# 1-Schematic_electronic_khipu_2.net
KiCad netlist of a schematic drawn in EasyEDA
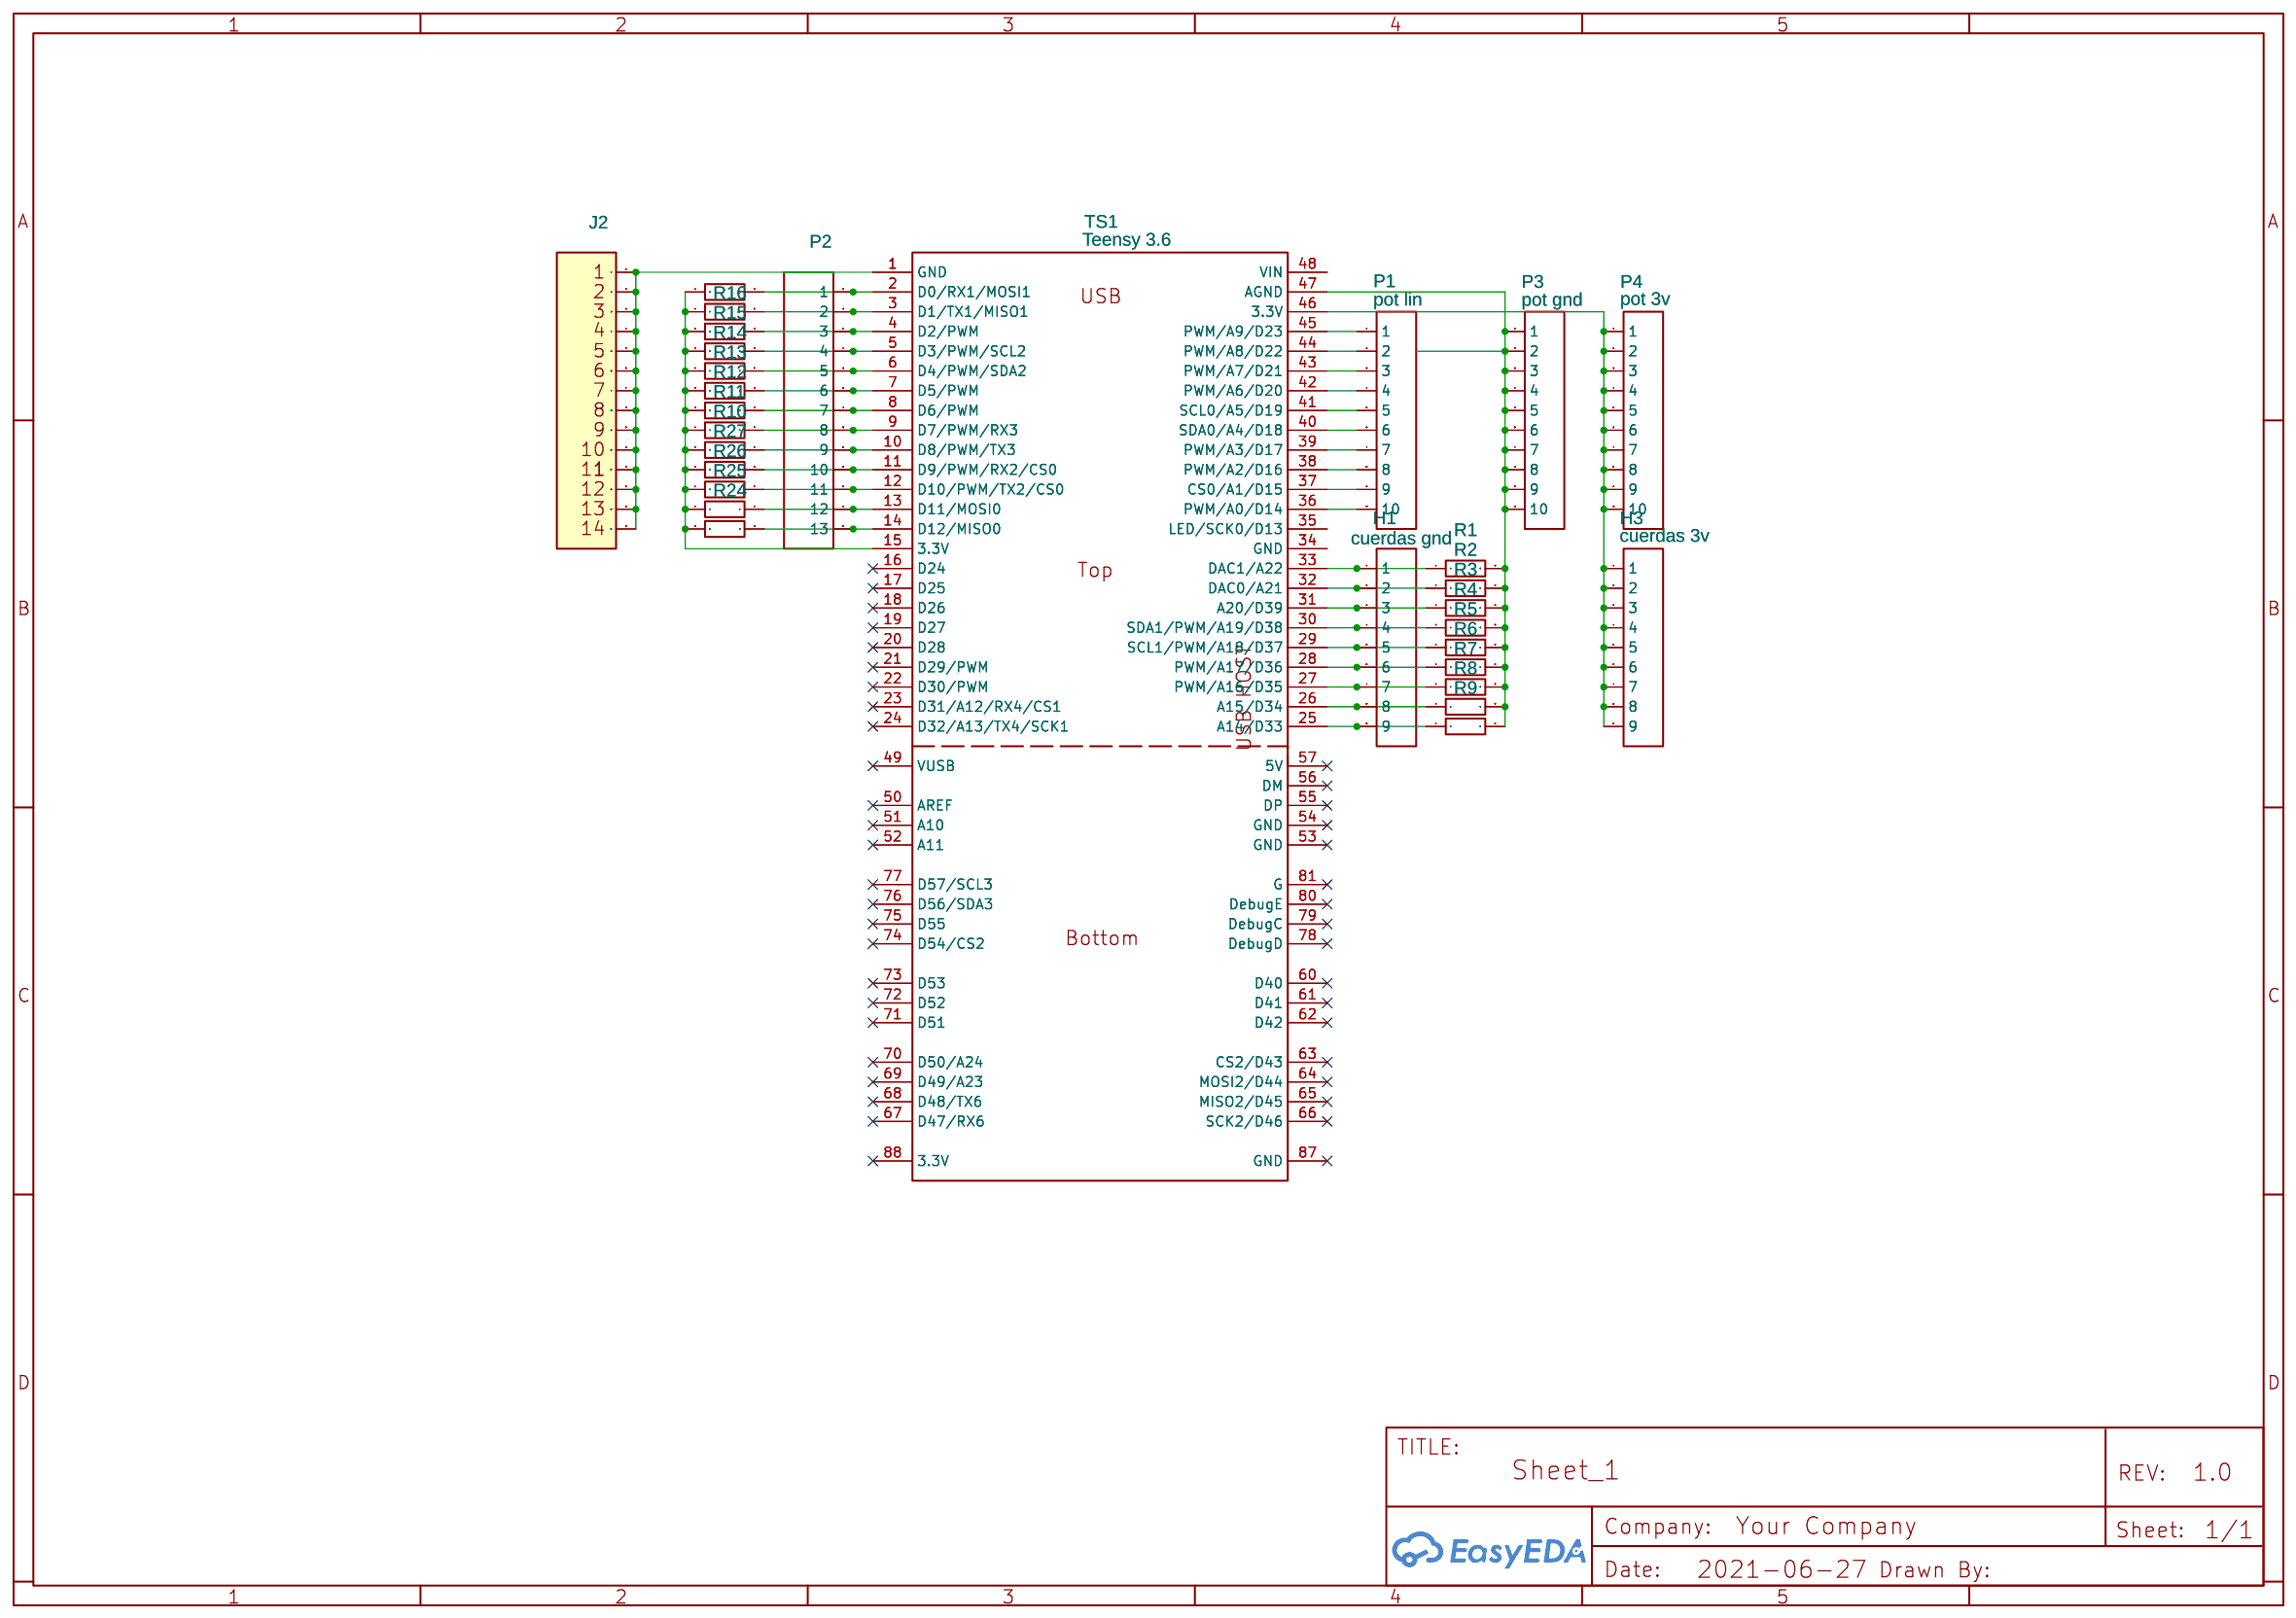
[diagram p0: schematic sheet]

(export (version "E")
  (design (tool "Eeschema 10.0.6"))
  (components
    (comp (ref "H1")
      (value "cuerdas gnd")
      (fields
        (field (name "BOM_Manufacturer Part") "2.54mm 1*9 Straight Female header")
        (field (name "BOM_Supplier Part") "C39576")
      )
      (libsource (lib "") (part "Header-Female-2.54_1x9"))
    )
    (comp (ref "H3")
      (value "cuerdas 3v")
      (fields
        (field (name "BOM_Manufacturer Part") "2.54mm 1*9 Straight Female header")
        (field (name "BOM_Supplier Part") "C39576")
      )
      (libsource (lib "") (part "Header-Female-2.54_1x9"))
    )
    (comp (ref "J2") (value "Header_Female_1x14") (libsource (lib "") (part "Header_Female_1x14")))
    (comp (ref "P1")
      (value "pot lin")
      (fields
        (field (name "BOM_Manufacturer Part") "2.54mm 1*10P Straight Female header Gold-plated")
        (field (name "BOM_Supplier Part") "C35445")
      )
      (libsource (lib "") (part "Header-Female-2.54_1x10-TEST"))
    )
    (comp (ref "P2")
      (value "Header-Female-2.54_1x13")
      (fields
        (field (name "BOM_Manufacturer Part") "Female header 2.54-1*13P")
        (field (name "BOM_Supplier Part") "C52709")
      )
      (libsource (lib "") (part "Header-Female-2.54_1x13"))
    )
    (comp (ref "P3")
      (value "pot gnd")
      (fields
        (field (name "BOM_Manufacturer Part") "2.54mm 1*10P Straight Female header Gold-plated")
        (field (name "BOM_Supplier Part") "C35445")
      )
      (libsource (lib "") (part "Header-Female-2.54_1x10-TEST"))
    )
    (comp (ref "P4")
      (value "pot 3v")
      (fields
        (field (name "BOM_Manufacturer Part") "2.54mm 1*10P Straight Female header Gold-plated")
        (field (name "BOM_Supplier Part") "C35445")
      )
      (libsource (lib "") (part "Header-Female-2.54_1x10-TEST"))
    )
    (comp (ref "R1")
      (value "10K")
      (fields
        (field (name "BOM_Manufacturer Part") "PTFR0603B10K0P9")
        (field (name "BOM_Supplier Part") "C328421")
      )
      (libsource (lib "") (part "PTFR0603B10K0P9"))
    )
    (comp (ref "R2")
      (value "10K")
      (fields
        (field (name "BOM_Manufacturer Part") "PTFR0603B10K0P9")
        (field (name "BOM_Supplier Part") "C328421")
      )
      (libsource (lib "") (part "PTFR0603B10K0P9"))
    )
    (comp (ref "R3")
      (value "10K")
      (fields
        (field (name "BOM_Manufacturer Part") "PTFR0603B10K0P9")
        (field (name "BOM_Supplier Part") "C328421")
      )
      (libsource (lib "") (part "PTFR0603B10K0P9"))
    )
    (comp (ref "R4")
      (value "10K")
      (fields
        (field (name "BOM_Manufacturer Part") "PTFR0603B10K0P9")
        (field (name "BOM_Supplier Part") "C328421")
      )
      (libsource (lib "") (part "PTFR0603B10K0P9"))
    )
    (comp (ref "R5")
      (value "10K")
      (fields
        (field (name "BOM_Manufacturer Part") "PTFR0603B10K0P9")
        (field (name "BOM_Supplier Part") "C328421")
      )
      (libsource (lib "") (part "PTFR0603B10K0P9"))
    )
    (comp (ref "R6")
      (value "10K")
      (fields
        (field (name "BOM_Manufacturer Part") "PTFR0603B10K0P9")
        (field (name "BOM_Supplier Part") "C328421")
      )
      (libsource (lib "") (part "PTFR0603B10K0P9"))
    )
    (comp (ref "R7")
      (value "10K")
      (fields
        (field (name "BOM_Manufacturer Part") "PTFR0603B10K0P9")
        (field (name "BOM_Supplier Part") "C328421")
      )
      (libsource (lib "") (part "PTFR0603B10K0P9"))
    )
    (comp (ref "R8")
      (value "10K")
      (fields
        (field (name "BOM_Manufacturer Part") "PTFR0603B10K0P9")
        (field (name "BOM_Supplier Part") "C328421")
      )
      (libsource (lib "") (part "PTFR0603B10K0P9"))
    )
    (comp (ref "R9")
      (value "10K")
      (fields
        (field (name "BOM_Manufacturer Part") "PTFR0603B10K0P9")
        (field (name "BOM_Supplier Part") "C328421")
      )
      (libsource (lib "") (part "PTFR0603B10K0P9"))
    )
    (comp (ref "R10")
      (value "10K")
      (fields
        (field (name "BOM_Manufacturer Part") "PTFR0603B10K0P9")
        (field (name "BOM_Supplier Part") "C328421")
      )
      (libsource (lib "") (part "PTFR0603B10K0P9"))
    )
    (comp (ref "R11")
      (value "10K")
      (fields
        (field (name "BOM_Manufacturer Part") "PTFR0603B10K0P9")
        (field (name "BOM_Supplier Part") "C328421")
      )
      (libsource (lib "") (part "PTFR0603B10K0P9"))
    )
    (comp (ref "R12")
      (value "10K")
      (fields
        (field (name "BOM_Manufacturer Part") "PTFR0603B10K0P9")
        (field (name "BOM_Supplier Part") "C328421")
      )
      (libsource (lib "") (part "PTFR0603B10K0P9"))
    )
    (comp (ref "R13")
      (value "10K")
      (fields
        (field (name "BOM_Manufacturer Part") "PTFR0603B10K0P9")
        (field (name "BOM_Supplier Part") "C328421")
      )
      (libsource (lib "") (part "PTFR0603B10K0P9"))
    )
    (comp (ref "R14")
      (value "10K")
      (fields
        (field (name "BOM_Manufacturer Part") "PTFR0603B10K0P9")
        (field (name "BOM_Supplier Part") "C328421")
      )
      (libsource (lib "") (part "PTFR0603B10K0P9"))
    )
    (comp (ref "R15")
      (value "10K")
      (fields
        (field (name "BOM_Manufacturer Part") "PTFR0603B10K0P9")
        (field (name "BOM_Supplier Part") "C328421")
      )
      (libsource (lib "") (part "PTFR0603B10K0P9"))
    )
    (comp (ref "R16")
      (value "10K")
      (fields
        (field (name "BOM_Manufacturer Part") "PTFR0603B10K0P9")
        (field (name "BOM_Supplier Part") "C328421")
      )
      (libsource (lib "") (part "PTFR0603B10K0P9"))
    )
    (comp (ref "R17")
      (value "10K")
      (fields
        (field (name "BOM_Manufacturer Part") "PTFR0603B10K0P9")
        (field (name "BOM_Supplier Part") "C328421")
      )
      (libsource (lib "") (part "PTFR0603B10K0P9"))
    )
    (comp (ref "R18")
      (value "10K")
      (fields
        (field (name "BOM_Manufacturer Part") "PTFR0603B10K0P9")
        (field (name "BOM_Supplier Part") "C328421")
      )
      (libsource (lib "") (part "PTFR0603B10K0P9"))
    )
    (comp (ref "R24")
      (value "10K")
      (fields
        (field (name "BOM_Manufacturer Part") "PTFR0603B10K0P9")
        (field (name "BOM_Supplier Part") "C328421")
      )
      (libsource (lib "") (part "PTFR0603B10K0P9"))
    )
    (comp (ref "R25")
      (value "10K")
      (fields
        (field (name "BOM_Manufacturer Part") "PTFR0603B10K0P9")
        (field (name "BOM_Supplier Part") "C328421")
      )
      (libsource (lib "") (part "PTFR0603B10K0P9"))
    )
    (comp (ref "R26")
      (value "10K")
      (fields
        (field (name "BOM_Manufacturer Part") "PTFR0603B10K0P9")
        (field (name "BOM_Supplier Part") "C328421")
      )
      (libsource (lib "") (part "PTFR0603B10K0P9"))
    )
    (comp (ref "R27")
      (value "10K")
      (fields
        (field (name "BOM_Manufacturer Part") "PTFR0603B10K0P9")
        (field (name "BOM_Supplier Part") "C328421")
      )
      (libsource (lib "") (part "PTFR0603B10K0P9"))
    )
    (comp (ref "TS1")
      (value "Teensy 3.6")
      (fields (field (name "BOM_Manufacturer Part") "TEENSY36"))
      (libsource (lib "") (part "Teensy 3.6"))
    )
  )
  (nets
    (net (code "1") (name "Net-(H3-Pad1)") (class "Default")
      (node (ref "H3") (pin "1") (pinfunction "1_1") (pintype "input"))
      (node (ref "H3") (pin "2") (pinfunction "2_2") (pintype "input"))
      (node (ref "H3") (pin "3") (pinfunction "3_3") (pintype "input"))
      (node (ref "H3") (pin "4") (pinfunction "4_4") (pintype "input"))
      (node (ref "H3") (pin "5") (pinfunction "5_5") (pintype "input"))
      (node (ref "H3") (pin "6") (pinfunction "6_6") (pintype "input"))
      (node (ref "H3") (pin "7") (pinfunction "7_7") (pintype "input"))
      (node (ref "H3") (pin "8") (pinfunction "8_8") (pintype "input"))
      (node (ref "H3") (pin "9") (pinfunction "9_9") (pintype "input"))
      (node (ref "P4") (pin "1") (pinfunction "1_1") (pintype "input"))
      (node (ref "P4") (pin "10") (pinfunction "10_10") (pintype "input"))
      (node (ref "P4") (pin "2") (pinfunction "2_2") (pintype "input"))
      (node (ref "P4") (pin "3") (pinfunction "3_3") (pintype "input"))
      (node (ref "P4") (pin "4") (pinfunction "4_4") (pintype "input"))
      (node (ref "P4") (pin "5") (pinfunction "5_5") (pintype "input"))
      (node (ref "P4") (pin "6") (pinfunction "6_6") (pintype "input"))
      (node (ref "P4") (pin "7") (pinfunction "7_7") (pintype "input"))
      (node (ref "P4") (pin "8") (pinfunction "8_8") (pintype "input"))
      (node (ref "P4") (pin "9") (pinfunction "9_9") (pintype "input"))
      (node (ref "TS1") (pin "46") (pinfunction "3.3V_46") (pintype "unspecified"))
    )
    (net (code "2") (name "Net-(J2-Pad1)") (class "Default")
      (node (ref "J2") (pin "1") (pinfunction "1_1") (pintype "unspecified"))
      (node (ref "J2") (pin "10") (pinfunction "10_10") (pintype "unspecified"))
      (node (ref "J2") (pin "11") (pinfunction "11_11") (pintype "unspecified"))
      (node (ref "J2") (pin "12") (pinfunction "12_12") (pintype "unspecified"))
      (node (ref "J2") (pin "13") (pinfunction "13_13") (pintype "unspecified"))
      (node (ref "J2") (pin "14") (pinfunction "14_14") (pintype "unspecified"))
      (node (ref "J2") (pin "2") (pinfunction "2_2") (pintype "unspecified"))
      (node (ref "J2") (pin "3") (pinfunction "3_3") (pintype "unspecified"))
      (node (ref "J2") (pin "4") (pinfunction "4_4") (pintype "unspecified"))
      (node (ref "J2") (pin "5") (pinfunction "5_5") (pintype "unspecified"))
      (node (ref "J2") (pin "6") (pinfunction "6_6") (pintype "unspecified"))
      (node (ref "J2") (pin "7") (pinfunction "7_7") (pintype "unspecified"))
      (node (ref "J2") (pin "8") (pinfunction "8_8") (pintype "unspecified"))
      (node (ref "J2") (pin "9") (pinfunction "9_9") (pintype "unspecified"))
      (node (ref "TS1") (pin "1") (pinfunction "GND_1") (pintype "unspecified"))
    )
    (net (code "3") (name "Net-(R10-Pad1)") (class "Default")
      (node (ref "R10") (pin "1") (pinfunction "1_1") (pintype "unspecified"))
      (node (ref "R11") (pin "1") (pinfunction "1_1") (pintype "unspecified"))
      (node (ref "R12") (pin "1") (pinfunction "1_1") (pintype "unspecified"))
      (node (ref "R13") (pin "1") (pinfunction "1_1") (pintype "unspecified"))
      (node (ref "R14") (pin "1") (pinfunction "1_1") (pintype "unspecified"))
      (node (ref "R15") (pin "1") (pinfunction "1_1") (pintype "unspecified"))
      (node (ref "R16") (pin "1") (pinfunction "1_1") (pintype "unspecified"))
      (node (ref "R17") (pin "1") (pinfunction "1_1") (pintype "unspecified"))
      (node (ref "R18") (pin "1") (pinfunction "1_1") (pintype "unspecified"))
      (node (ref "R24") (pin "1") (pinfunction "1_1") (pintype "unspecified"))
      (node (ref "R25") (pin "1") (pinfunction "1_1") (pintype "unspecified"))
      (node (ref "R26") (pin "1") (pinfunction "1_1") (pintype "unspecified"))
      (node (ref "R27") (pin "1") (pinfunction "1_1") (pintype "unspecified"))
      (node (ref "TS1") (pin "15") (pinfunction "3.3V_15") (pintype "unspecified"))
    )
    (net (code "4") (name "Net-(TS1-A14{slash}D33)") (class "Default")
      (node (ref "H1") (pin "9") (pinfunction "9_9") (pintype "input"))
      (node (ref "R9") (pin "1") (pinfunction "1_1") (pintype "unspecified"))
      (node (ref "TS1") (pin "25") (pinfunction "A14/D33_25") (pintype "unspecified"))
    )
    (net (code "5") (name "Net-(TS1-A15{slash}D34)") (class "Default")
      (node (ref "H1") (pin "8") (pinfunction "8_8") (pintype "input"))
      (node (ref "R8") (pin "1") (pinfunction "1_1") (pintype "unspecified"))
      (node (ref "TS1") (pin "26") (pinfunction "A15/D34_26") (pintype "unspecified"))
    )
    (net (code "6") (name "Net-(TS1-A20{slash}D39)") (class "Default")
      (node (ref "H1") (pin "3") (pinfunction "3_3") (pintype "input"))
      (node (ref "R3") (pin "1") (pinfunction "1_1") (pintype "unspecified"))
      (node (ref "TS1") (pin "31") (pinfunction "A20/D39_31") (pintype "unspecified"))
    )
    (net (code "7") (name "Net-(TS1-AGND)") (class "Default")
      (node (ref "P3") (pin "1") (pinfunction "1_1") (pintype "input"))
      (node (ref "P3") (pin "10") (pinfunction "10_10") (pintype "input"))
      (node (ref "P3") (pin "2") (pinfunction "2_2") (pintype "input"))
      (node (ref "P3") (pin "3") (pinfunction "3_3") (pintype "input"))
      (node (ref "P3") (pin "4") (pinfunction "4_4") (pintype "input"))
      (node (ref "P3") (pin "5") (pinfunction "5_5") (pintype "input"))
      (node (ref "P3") (pin "6") (pinfunction "6_6") (pintype "input"))
      (node (ref "P3") (pin "7") (pinfunction "7_7") (pintype "input"))
      (node (ref "P3") (pin "8") (pinfunction "8_8") (pintype "input"))
      (node (ref "P3") (pin "9") (pinfunction "9_9") (pintype "input"))
      (node (ref "R1") (pin "2") (pinfunction "2_2") (pintype "unspecified"))
      (node (ref "R2") (pin "2") (pinfunction "2_2") (pintype "unspecified"))
      (node (ref "R3") (pin "2") (pinfunction "2_2") (pintype "unspecified"))
      (node (ref "R4") (pin "2") (pinfunction "2_2") (pintype "unspecified"))
      (node (ref "R5") (pin "2") (pinfunction "2_2") (pintype "unspecified"))
      (node (ref "R6") (pin "2") (pinfunction "2_2") (pintype "unspecified"))
      (node (ref "R7") (pin "2") (pinfunction "2_2") (pintype "unspecified"))
      (node (ref "R8") (pin "2") (pinfunction "2_2") (pintype "unspecified"))
      (node (ref "R9") (pin "2") (pinfunction "2_2") (pintype "unspecified"))
      (node (ref "TS1") (pin "47") (pinfunction "AGND_47") (pintype "unspecified"))
    )
    (net (code "8") (name "Net-(TS1-CS0{slash}A1{slash}D15)") (class "Default")
      (node (ref "P1") (pin "9") (pinfunction "9_9") (pintype "input"))
      (node (ref "TS1") (pin "37") (pinfunction "CS0/A1/D15_37") (pintype "unspecified"))
    )
    (net (code "9") (name "Net-(TS1-D0{slash}RX1{slash}MOSI1)") (class "Default")
      (node (ref "P2") (pin "1") (pinfunction "1_1") (pintype "input"))
      (node (ref "R18") (pin "2") (pinfunction "2_2") (pintype "unspecified"))
      (node (ref "TS1") (pin "2") (pinfunction "D0/RX1/MOSI1_2") (pintype "unspecified"))
    )
    (net (code "10") (name "Net-(TS1-D1{slash}TX1{slash}MISO1)") (class "Default")
      (node (ref "P2") (pin "2") (pinfunction "2_2") (pintype "input"))
      (node (ref "R17") (pin "2") (pinfunction "2_2") (pintype "unspecified"))
      (node (ref "TS1") (pin "3") (pinfunction "D1/TX1/MISO1_3") (pintype "unspecified"))
    )
    (net (code "11") (name "Net-(TS1-D2{slash}PWM)") (class "Default")
      (node (ref "P2") (pin "3") (pinfunction "3_3") (pintype "input"))
      (node (ref "R16") (pin "2") (pinfunction "2_2") (pintype "unspecified"))
      (node (ref "TS1") (pin "4") (pinfunction "D2/PWM_4") (pintype "unspecified"))
    )
    (net (code "12") (name "Net-(TS1-D3{slash}PWM{slash}SCL2)") (class "Default")
      (node (ref "P2") (pin "4") (pinfunction "4_4") (pintype "input"))
      (node (ref "R15") (pin "2") (pinfunction "2_2") (pintype "unspecified"))
      (node (ref "TS1") (pin "5") (pinfunction "D3/PWM/SCL2_5") (pintype "unspecified"))
    )
    (net (code "13") (name "Net-(TS1-D4{slash}PWM{slash}SDA2)") (class "Default")
      (node (ref "P2") (pin "5") (pinfunction "5_5") (pintype "input"))
      (node (ref "R14") (pin "2") (pinfunction "2_2") (pintype "unspecified"))
      (node (ref "TS1") (pin "6") (pinfunction "D4/PWM/SDA2_6") (pintype "unspecified"))
    )
    (net (code "14") (name "Net-(TS1-D5{slash}PWM)") (class "Default")
      (node (ref "P2") (pin "6") (pinfunction "6_6") (pintype "input"))
      (node (ref "R13") (pin "2") (pinfunction "2_2") (pintype "unspecified"))
      (node (ref "TS1") (pin "7") (pinfunction "D5/PWM_7") (pintype "unspecified"))
    )
    (net (code "15") (name "Net-(TS1-D6{slash}PWM)") (class "Default")
      (node (ref "P2") (pin "7") (pinfunction "7_7") (pintype "input"))
      (node (ref "R12") (pin "2") (pinfunction "2_2") (pintype "unspecified"))
      (node (ref "TS1") (pin "8") (pinfunction "D6/PWM_8") (pintype "unspecified"))
    )
    (net (code "16") (name "Net-(TS1-D7{slash}PWM{slash}RX3)") (class "Default")
      (node (ref "P2") (pin "8") (pinfunction "8_8") (pintype "input"))
      (node (ref "R11") (pin "2") (pinfunction "2_2") (pintype "unspecified"))
      (node (ref "TS1") (pin "9") (pinfunction "D7/PWM/RX3_9") (pintype "unspecified"))
    )
    (net (code "17") (name "Net-(TS1-D8{slash}PWM{slash}TX3)") (class "Default")
      (node (ref "P2") (pin "9") (pinfunction "9_9") (pintype "input"))
      (node (ref "R10") (pin "2") (pinfunction "2_2") (pintype "unspecified"))
      (node (ref "TS1") (pin "10") (pinfunction "D8/PWM/TX3_10") (pintype "unspecified"))
    )
    (net (code "18") (name "Net-(TS1-D9{slash}PWM{slash}RX2{slash}CS0)") (class "Default")
      (node (ref "P2") (pin "10") (pinfunction "10_10") (pintype "input"))
      (node (ref "R27") (pin "2") (pinfunction "2_2") (pintype "unspecified"))
      (node (ref "TS1") (pin "11") (pinfunction "D9/PWM/RX2/CS0_11") (pintype "unspecified"))
    )
    (net (code "19") (name "Net-(TS1-D10{slash}PWM{slash}TX2{slash}CS0)") (class "Default")
      (node (ref "P2") (pin "11") (pinfunction "11_11") (pintype "input"))
      (node (ref "R26") (pin "2") (pinfunction "2_2") (pintype "unspecified"))
      (node (ref "TS1") (pin "12") (pinfunction "D10/PWM/TX2/CS0_12") (pintype "unspecified"))
    )
    (net (code "20") (name "Net-(TS1-D11{slash}MOSI0)") (class "Default")
      (node (ref "P2") (pin "12") (pinfunction "12_12") (pintype "input"))
      (node (ref "R25") (pin "2") (pinfunction "2_2") (pintype "unspecified"))
      (node (ref "TS1") (pin "13") (pinfunction "D11/MOSI0_13") (pintype "unspecified"))
    )
    (net (code "21") (name "Net-(TS1-D12{slash}MISO0)") (class "Default")
      (node (ref "P2") (pin "13") (pinfunction "13_13") (pintype "input"))
      (node (ref "R24") (pin "2") (pinfunction "2_2") (pintype "unspecified"))
      (node (ref "TS1") (pin "14") (pinfunction "D12/MISO0_14") (pintype "unspecified"))
    )
    (net (code "22") (name "Net-(TS1-DAC0{slash}A21)") (class "Default")
      (node (ref "H1") (pin "2") (pinfunction "2_2") (pintype "input"))
      (node (ref "R2") (pin "1") (pinfunction "1_1") (pintype "unspecified"))
      (node (ref "TS1") (pin "32") (pinfunction "DAC0/A21_32") (pintype "unspecified"))
    )
    (net (code "23") (name "Net-(TS1-DAC1{slash}A22)") (class "Default")
      (node (ref "H1") (pin "1") (pinfunction "1_1") (pintype "input"))
      (node (ref "R1") (pin "1") (pinfunction "1_1") (pintype "unspecified"))
      (node (ref "TS1") (pin "33") (pinfunction "DAC1/A22_33") (pintype "unspecified"))
    )
    (net (code "24") (name "Net-(TS1-PWM{slash}A0{slash}D14)") (class "Default")
      (node (ref "P1") (pin "10") (pinfunction "10_10") (pintype "input"))
      (node (ref "TS1") (pin "36") (pinfunction "PWM/A0/D14_36") (pintype "unspecified"))
    )
    (net (code "25") (name "Net-(TS1-PWM{slash}A2{slash}D16)") (class "Default")
      (node (ref "P1") (pin "8") (pinfunction "8_8") (pintype "input"))
      (node (ref "TS1") (pin "38") (pinfunction "PWM/A2/D16_38") (pintype "unspecified"))
    )
    (net (code "26") (name "Net-(TS1-PWM{slash}A3{slash}D17)") (class "Default")
      (node (ref "P1") (pin "7") (pinfunction "7_7") (pintype "input"))
      (node (ref "TS1") (pin "39") (pinfunction "PWM/A3/D17_39") (pintype "unspecified"))
    )
    (net (code "27") (name "Net-(TS1-PWM{slash}A6{slash}D20)") (class "Default")
      (node (ref "P1") (pin "4") (pinfunction "4_4") (pintype "input"))
      (node (ref "TS1") (pin "42") (pinfunction "PWM/A6/D20_42") (pintype "unspecified"))
    )
    (net (code "28") (name "Net-(TS1-PWM{slash}A7{slash}D21)") (class "Default")
      (node (ref "P1") (pin "3") (pinfunction "3_3") (pintype "input"))
      (node (ref "TS1") (pin "43") (pinfunction "PWM/A7/D21_43") (pintype "unspecified"))
    )
    (net (code "29") (name "Net-(TS1-PWM{slash}A8{slash}D22)") (class "Default")
      (node (ref "P1") (pin "2") (pinfunction "2_2") (pintype "input"))
      (node (ref "TS1") (pin "44") (pinfunction "PWM/A8/D22_44") (pintype "unspecified"))
    )
    (net (code "30") (name "Net-(TS1-PWM{slash}A9{slash}D23)") (class "Default")
      (node (ref "P1") (pin "1") (pinfunction "1_1") (pintype "input"))
      (node (ref "TS1") (pin "45") (pinfunction "PWM/A9/D23_45") (pintype "unspecified"))
    )
    (net (code "31") (name "Net-(TS1-PWM{slash}A16{slash}D35)") (class "Default")
      (node (ref "H1") (pin "7") (pinfunction "7_7") (pintype "input"))
      (node (ref "R7") (pin "1") (pinfunction "1_1") (pintype "unspecified"))
      (node (ref "TS1") (pin "27") (pinfunction "PWM/A16/D35_27") (pintype "unspecified"))
    )
    (net (code "32") (name "Net-(TS1-PWM{slash}A17{slash}D36)") (class "Default")
      (node (ref "H1") (pin "6") (pinfunction "6_6") (pintype "input"))
      (node (ref "R6") (pin "1") (pinfunction "1_1") (pintype "unspecified"))
      (node (ref "TS1") (pin "28") (pinfunction "PWM/A17/D36_28") (pintype "unspecified"))
    )
    (net (code "33") (name "Net-(TS1-SCL0{slash}A5{slash}D19)") (class "Default")
      (node (ref "P1") (pin "5") (pinfunction "5_5") (pintype "input"))
      (node (ref "TS1") (pin "41") (pinfunction "SCL0/A5/D19_41") (pintype "unspecified"))
    )
    (net (code "34") (name "Net-(TS1-SCL1{slash}PWM{slash}A18{slash}D37)") (class "Default")
      (node (ref "H1") (pin "5") (pinfunction "5_5") (pintype "input"))
      (node (ref "R5") (pin "1") (pinfunction "1_1") (pintype "unspecified"))
      (node (ref "TS1") (pin "29") (pinfunction "SCL1/PWM/A18/D37_29") (pintype "unspecified"))
    )
    (net (code "35") (name "Net-(TS1-SDA0{slash}A4{slash}D18)") (class "Default")
      (node (ref "P1") (pin "6") (pinfunction "6_6") (pintype "input"))
      (node (ref "TS1") (pin "40") (pinfunction "SDA0/A4/D18_40") (pintype "unspecified"))
    )
    (net (code "36") (name "Net-(TS1-SDA1{slash}PWM{slash}A19{slash}D38)") (class "Default")
      (node (ref "H1") (pin "4") (pinfunction "4_4") (pintype "input"))
      (node (ref "R4") (pin "1") (pinfunction "1_1") (pintype "unspecified"))
      (node (ref "TS1") (pin "30") (pinfunction "SDA1/PWM/A19/D38_30") (pintype "unspecified"))
    )
    (net (code "37") (name "unconnected-(TS1-3.3V-Pad88)") (class "Default")
      (node (ref "TS1") (pin "88") (pinfunction "3.3V_88") (pintype "unspecified+no_connect"))
    )
    (net (code "38") (name "unconnected-(TS1-5V-Pad57)") (class "Default")
      (node (ref "TS1") (pin "57") (pinfunction "5V_57") (pintype "unspecified+no_connect"))
    )
    (net (code "39") (name "unconnected-(TS1-A10-Pad51)") (class "Default")
      (node (ref "TS1") (pin "51") (pinfunction "A10_51") (pintype "unspecified+no_connect"))
    )
    (net (code "40") (name "unconnected-(TS1-A11-Pad52)") (class "Default")
      (node (ref "TS1") (pin "52") (pinfunction "A11_52") (pintype "unspecified+no_connect"))
    )
    (net (code "41") (name "unconnected-(TS1-AREF-Pad50)") (class "Default")
      (node (ref "TS1") (pin "50") (pinfunction "AREF_50") (pintype "unspecified+no_connect"))
    )
    (net (code "42") (name "unconnected-(TS1-CS2{slash}D43-Pad63)") (class "Default")
      (node (ref "TS1") (pin "63") (pinfunction "CS2/D43_63") (pintype "unspecified+no_connect"))
    )
    (net (code "43") (name "unconnected-(TS1-D24-Pad16)") (class "Default")
      (node (ref "TS1") (pin "16") (pinfunction "D24_16") (pintype "unspecified+no_connect"))
    )
    (net (code "44") (name "unconnected-(TS1-D25-Pad17)") (class "Default")
      (node (ref "TS1") (pin "17") (pinfunction "D25_17") (pintype "unspecified+no_connect"))
    )
    (net (code "45") (name "unconnected-(TS1-D26-Pad18)") (class "Default")
      (node (ref "TS1") (pin "18") (pinfunction "D26_18") (pintype "unspecified+no_connect"))
    )
    (net (code "46") (name "unconnected-(TS1-D27-Pad19)") (class "Default")
      (node (ref "TS1") (pin "19") (pinfunction "D27_19") (pintype "unspecified+no_connect"))
    )
    (net (code "47") (name "unconnected-(TS1-D28-Pad20)") (class "Default")
      (node (ref "TS1") (pin "20") (pinfunction "D28_20") (pintype "unspecified+no_connect"))
    )
    (net (code "48") (name "unconnected-(TS1-D29{slash}PWM-Pad21)") (class "Default")
      (node (ref "TS1") (pin "21") (pinfunction "D29/PWM_21") (pintype "unspecified+no_connect"))
    )
    (net (code "49") (name "unconnected-(TS1-D30{slash}PWM-Pad22)") (class "Default")
      (node (ref "TS1") (pin "22") (pinfunction "D30/PWM_22") (pintype "unspecified+no_connect"))
    )
    (net (code "50") (name "unconnected-(TS1-D31{slash}A12{slash}RX4{slash}CS1-Pad23)") (class "Default")
      (node (ref "TS1") (pin "23") (pinfunction "D31/A12/RX4/CS1_23") (pintype "unspecified+no_connect"))
    )
    (net (code "51") (name "unconnected-(TS1-D32{slash}A13{slash}TX4{slash}SCK1-Pad24)") (class "Default")
      (node (ref "TS1") (pin "24") (pinfunction "D32/A13/TX4/SCK1_24") (pintype "unspecified+no_connect"))
    )
    (net (code "52") (name "unconnected-(TS1-D40-Pad60)") (class "Default")
      (node (ref "TS1") (pin "60") (pinfunction "D40_60") (pintype "unspecified+no_connect"))
    )
    (net (code "53") (name "unconnected-(TS1-D41-Pad61)") (class "Default")
      (node (ref "TS1") (pin "61") (pinfunction "D41_61") (pintype "unspecified+no_connect"))
    )
    (net (code "54") (name "unconnected-(TS1-D42-Pad62)") (class "Default")
      (node (ref "TS1") (pin "62") (pinfunction "D42_62") (pintype "unspecified+no_connect"))
    )
    (net (code "55") (name "unconnected-(TS1-D47{slash}RX6-Pad67)") (class "Default")
      (node (ref "TS1") (pin "67") (pinfunction "D47/RX6_67") (pintype "unspecified+no_connect"))
    )
    (net (code "56") (name "unconnected-(TS1-D48{slash}TX6-Pad68)") (class "Default")
      (node (ref "TS1") (pin "68") (pinfunction "D48/TX6_68") (pintype "unspecified+no_connect"))
    )
    (net (code "57") (name "unconnected-(TS1-D49{slash}A23-Pad69)") (class "Default")
      (node (ref "TS1") (pin "69") (pinfunction "D49/A23_69") (pintype "unspecified+no_connect"))
    )
    (net (code "58") (name "unconnected-(TS1-D50{slash}A24-Pad70)") (class "Default")
      (node (ref "TS1") (pin "70") (pinfunction "D50/A24_70") (pintype "unspecified+no_connect"))
    )
    (net (code "59") (name "unconnected-(TS1-D51-Pad71)") (class "Default")
      (node (ref "TS1") (pin "71") (pinfunction "D51_71") (pintype "unspecified+no_connect"))
    )
    (net (code "60") (name "unconnected-(TS1-D52-Pad72)") (class "Default")
      (node (ref "TS1") (pin "72") (pinfunction "D52_72") (pintype "unspecified+no_connect"))
    )
    (net (code "61") (name "unconnected-(TS1-D53-Pad73)") (class "Default")
      (node (ref "TS1") (pin "73") (pinfunction "D53_73") (pintype "unspecified+no_connect"))
    )
    (net (code "62") (name "unconnected-(TS1-D54{slash}CS2-Pad74)") (class "Default")
      (node (ref "TS1") (pin "74") (pinfunction "D54/CS2_74") (pintype "unspecified+no_connect"))
    )
    (net (code "63") (name "unconnected-(TS1-D55-Pad75)") (class "Default")
      (node (ref "TS1") (pin "75") (pinfunction "D55_75") (pintype "unspecified+no_connect"))
    )
    (net (code "64") (name "unconnected-(TS1-D56{slash}SDA3-Pad76)") (class "Default")
      (node (ref "TS1") (pin "76") (pinfunction "D56/SDA3_76") (pintype "unspecified+no_connect"))
    )
    (net (code "65") (name "unconnected-(TS1-D57{slash}SCL3-Pad77)") (class "Default")
      (node (ref "TS1") (pin "77") (pinfunction "D57/SCL3_77") (pintype "unspecified+no_connect"))
    )
    (net (code "66") (name "unconnected-(TS1-DM-Pad56)") (class "Default")
      (node (ref "TS1") (pin "56") (pinfunction "DM_56") (pintype "unspecified+no_connect"))
    )
    (net (code "67") (name "unconnected-(TS1-DP-Pad55)") (class "Default")
      (node (ref "TS1") (pin "55") (pinfunction "DP_55") (pintype "unspecified+no_connect"))
    )
    (net (code "68") (name "unconnected-(TS1-DebugC-Pad79)") (class "Default")
      (node (ref "TS1") (pin "79") (pinfunction "DebugC_79") (pintype "unspecified+no_connect"))
    )
    (net (code "69") (name "unconnected-(TS1-DebugD-Pad78)") (class "Default")
      (node (ref "TS1") (pin "78") (pinfunction "DebugD_78") (pintype "unspecified+no_connect"))
    )
    (net (code "70") (name "unconnected-(TS1-DebugE-Pad80)") (class "Default")
      (node (ref "TS1") (pin "80") (pinfunction "DebugE_80") (pintype "unspecified+no_connect"))
    )
    (net (code "71") (name "unconnected-(TS1-G-Pad81)") (class "Default")
      (node (ref "TS1") (pin "81") (pinfunction "G_81") (pintype "unspecified+no_connect"))
    )
    (net (code "72") (name "unconnected-(TS1-GND-Pad34)") (class "Default")
      (node (ref "TS1") (pin "34") (pinfunction "GND_34") (pintype "unspecified"))
    )
    (net (code "73") (name "unconnected-(TS1-GND-Pad53)") (class "Default")
      (node (ref "TS1") (pin "53") (pinfunction "GND_53") (pintype "unspecified+no_connect"))
    )
    (net (code "74") (name "unconnected-(TS1-GND-Pad54)") (class "Default")
      (node (ref "TS1") (pin "54") (pinfunction "GND_54") (pintype "unspecified+no_connect"))
    )
    (net (code "75") (name "unconnected-(TS1-GND-Pad87)") (class "Default")
      (node (ref "TS1") (pin "87") (pinfunction "GND_87") (pintype "unspecified+no_connect"))
    )
    (net (code "76") (name "unconnected-(TS1-LED{slash}SCK0{slash}D13-Pad35)") (class "Default")
      (node (ref "TS1") (pin "35") (pinfunction "LED/SCK0/D13_35") (pintype "unspecified"))
    )
    (net (code "77") (name "unconnected-(TS1-MISO2{slash}D45-Pad65)") (class "Default")
      (node (ref "TS1") (pin "65") (pinfunction "MISO2/D45_65") (pintype "unspecified+no_connect"))
    )
    (net (code "78") (name "unconnected-(TS1-MOSI2{slash}D44-Pad64)") (class "Default")
      (node (ref "TS1") (pin "64") (pinfunction "MOSI2/D44_64") (pintype "unspecified+no_connect"))
    )
    (net (code "79") (name "unconnected-(TS1-SCK2{slash}D46-Pad66)") (class "Default")
      (node (ref "TS1") (pin "66") (pinfunction "SCK2/D46_66") (pintype "unspecified+no_connect"))
    )
    (net (code "80") (name "unconnected-(TS1-VIN-Pad48)") (class "Default")
      (node (ref "TS1") (pin "48") (pinfunction "VIN_48") (pintype "unspecified"))
    )
    (net (code "81") (name "unconnected-(TS1-VUSB-Pad49)") (class "Default")
      (node (ref "TS1") (pin "49") (pinfunction "VUSB_49") (pintype "unspecified+no_connect"))
    )
  )
)
